# eeprom_temp_sens.net
KiCad netlist of a schematic drawn in Altium Designer
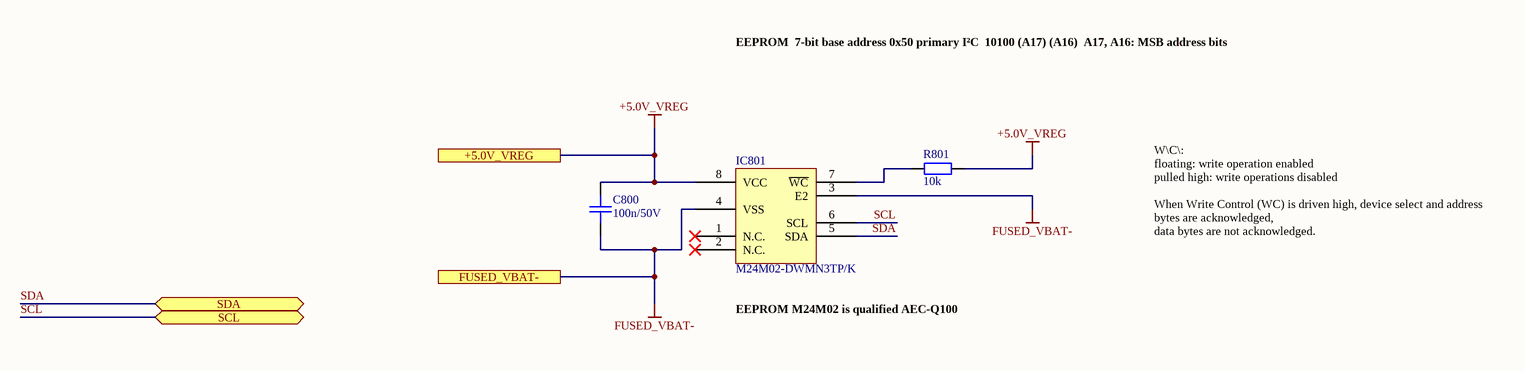
[diagram p0: eeprom_temp_sens.SchDoc]

(export (version "E")
  (design (tool "Eeschema 10.0.6"))
  (components
    (comp (ref "C800")
      (value "100n/50V")
      (footprint "CAPC1608X08N")
      (description "MLCC")
      (fields (field (name "PART NUMBER") "gen_C_ceramic_100n_50V_X7R_0603"))
      (libsource (lib "OE750") (part "C"))
    )
    (comp (ref "IC801")
      (value "M24M02-DWMN3TP/K")
      (footprint "SOIC127P600X175-8N")
      (description "Automotive 2-Mbit serial I²C \r\nbus EEPROM with 1 MHz clock")
      (fields (field (name "MANUFACTURER") "STMicroelectronics"))
      (libsource (lib "OE750") (part "M24M02-DWMN3TP/K"))
    )
    (comp (ref "R801")
      (value "10k")
      (footprint "RESC1608X05N")
      (description "SMD Resistor 10k 0603")
      (fields (field (name "PART NUMBER") "gen_R_10k_0603") (field (name "TOLERANCE") "1%"))
      (libsource (lib "OE750") (part "R"))
    )
  )
  (nets
    (net (code "1") (name "+5.0V_VREG") (class "Default")
      (node (ref "C800") (pin "2") (pinfunction "2_2") (pintype "passive"))
      (node (ref "IC801") (pin "8") (pinfunction "VCC_8") (pintype "power_in"))
      (node (ref "R801") (pin "2") (pinfunction "2_2") (pintype "passive"))
    )
    (net (code "2") (name "/SCL") (class "Default")
      (node (ref "IC801") (pin "6") (pinfunction "SCL_6") (pintype "passive"))
    )
    (net (code "3") (name "/SDA") (class "Default")
      (node (ref "IC801") (pin "5") (pinfunction "SDA_5") (pintype "passive"))
    )
    (net (code "4") (name "FUSED_VBAT-") (class "Default")
      (node (ref "C800") (pin "1") (pinfunction "1_1") (pintype "passive"))
      (node (ref "IC801") (pin "3") (pinfunction "E2_3") (pintype "passive"))
      (node (ref "IC801") (pin "4") (pinfunction "VSS_4") (pintype "power_in"))
    )
    (net (code "5") (name "Net-(IC801-~{WC})") (class "Default")
      (node (ref "IC801") (pin "7") (pinfunction "~{WC}_7") (pintype "passive"))
      (node (ref "R801") (pin "1") (pinfunction "1_1") (pintype "passive"))
    )
    (net (code "6") (name "unconnected-(IC801-N.C.-Pad1)") (class "Default")
      (node (ref "IC801") (pin "1") (pinfunction "N.C._1") (pintype "passive+no_connect"))
    )
    (net (code "7") (name "unconnected-(IC801-N.C.-Pad2)") (class "Default")
      (node (ref "IC801") (pin "2") (pinfunction "N.C._2") (pintype "passive+no_connect"))
    )
  )
)
